# lipo_charger.net
KiCad netlist of a schematic drawn in EAGLE
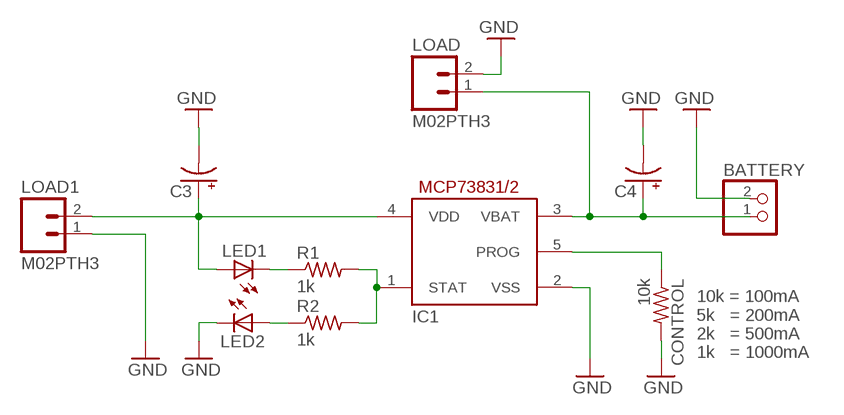
[diagram p0: schematic, sheet 1]

(export (version "E")
  (design (tool "Eeschema 10.0.6"))
  (components
    (comp (ref "BATTERY")
      (value "JST_2PIN-SMT-RA")
      (footprint "eagle-import:JST-PH-2-SMT-RA")
      (libsource (lib "eagle-import") (part "JST_2PIN-SMT-RA"))
    )
    (comp (ref "C3")
      (value "CAP_POL1206")
      (footprint "eagle-import:EIA3216")
      (libsource (lib "eagle-import") (part "CAP_POL1206"))
    )
    (comp (ref "C4")
      (value "CAP_POL1206")
      (footprint "eagle-import:EIA3216")
      (libsource (lib "eagle-import") (part "CAP_POL1206"))
    )
    (comp (ref "CONTROL")
      (value "10k")
      (footprint "eagle-import:R0603")
      (libsource (lib "eagle-import") (part "R-US_R0603"))
    )
    (comp (ref "IC1")
      (value "MCP73831/OT")
      (footprint "eagle-import:SOT23-5L")
      (libsource (lib "eagle-import") (part "MCP73831/OT"))
    )
    (comp (ref "LED1")
      (value "LEDCHIPLED_0603")
      (footprint "eagle-import:CHIPLED_0603")
      (libsource (lib "eagle-import") (part "LEDCHIPLED_0603"))
    )
    (comp (ref "LED2")
      (value "LEDCHIPLED_0603")
      (footprint "eagle-import:CHIPLED_0603")
      (libsource (lib "eagle-import") (part "LEDCHIPLED_0603"))
    )
    (comp (ref "LOAD")
      (value "M02PTH3")
      (footprint "eagle-import:1X02_LONGPADS")
      (libsource (lib "eagle-import") (part "M02PTH3"))
    )
    (comp (ref "LOAD1")
      (value "M02PTH3")
      (footprint "eagle-import:1X02_LONGPADS")
      (libsource (lib "eagle-import") (part "M02PTH3"))
    )
    (comp (ref "R1")
      (value "1k")
      (footprint "eagle-import:R0603")
      (libsource (lib "eagle-import") (part "R-US_R0603"))
    )
    (comp (ref "R2")
      (value "1k")
      (footprint "eagle-import:R0603")
      (libsource (lib "eagle-import") (part "R-US_R0603"))
    )
  )
  (nets
    (net (code "1") (name "GND") (class "Default")
      (node (ref "BATTERY") (pin "2") (pinfunction "1_2") (pintype "passive"))
      (node (ref "C3") (pin "C") (pinfunction "-_C") (pintype "passive"))
      (node (ref "C4") (pin "C") (pinfunction "-_C") (pintype "passive"))
      (node (ref "CONTROL") (pin "2") (pinfunction "2_2") (pintype "passive"))
      (node (ref "IC1") (pin "2") (pinfunction "VSS_2") (pintype "power_in"))
      (node (ref "LED2") (pin "C") (pinfunction "C_C") (pintype "passive"))
      (node (ref "LOAD") (pin "2") (pinfunction "2_2") (pintype "passive"))
      (node (ref "LOAD1") (pin "1") (pinfunction "1_1") (pintype "passive"))
    )
    (net (code "2") (name "Net-(BATTERY-2)") (class "Default")
      (node (ref "BATTERY") (pin "1") (pinfunction "2_1") (pintype "passive"))
      (node (ref "C4") (pin "A") (pinfunction "+_A") (pintype "passive"))
      (node (ref "IC1") (pin "3") (pinfunction "VBAT_3") (pintype "bidirectional"))
      (node (ref "LOAD") (pin "1") (pinfunction "1_1") (pintype "passive"))
    )
    (net (code "3") (name "Net-(C3-+)") (class "Default")
      (node (ref "C3") (pin "A") (pinfunction "+_A") (pintype "passive"))
      (node (ref "IC1") (pin "4") (pinfunction "VDD_4") (pintype "power_in"))
      (node (ref "LED1") (pin "A") (pinfunction "A_A") (pintype "passive"))
      (node (ref "LOAD1") (pin "2") (pinfunction "2_2") (pintype "passive"))
    )
    (net (code "4") (name "Net-(IC1-PROG)") (class "Default")
      (node (ref "CONTROL") (pin "1") (pinfunction "1_1") (pintype "passive"))
      (node (ref "IC1") (pin "5") (pinfunction "PROG_5") (pintype "input"))
    )
    (net (code "5") (name "Net-(IC1-STAT)") (class "Default")
      (node (ref "IC1") (pin "1") (pinfunction "STAT_1") (pintype "output"))
      (node (ref "R1") (pin "2") (pinfunction "2_2") (pintype "passive"))
      (node (ref "R2") (pin "2") (pinfunction "2_2") (pintype "passive"))
    )
    (net (code "6") (name "Net-(LED1-PadC)") (class "Default")
      (node (ref "LED1") (pin "C") (pinfunction "C_C") (pintype "passive"))
      (node (ref "R1") (pin "1") (pinfunction "1_1") (pintype "passive"))
    )
    (net (code "7") (name "Net-(LED2-PadA)") (class "Default")
      (node (ref "LED2") (pin "A") (pinfunction "A_A") (pintype "passive"))
      (node (ref "R2") (pin "1") (pinfunction "1_1") (pintype "passive"))
    )
  )
)
